# LEDboard.net
KiCad netlist of a schematic drawn in EAGLE
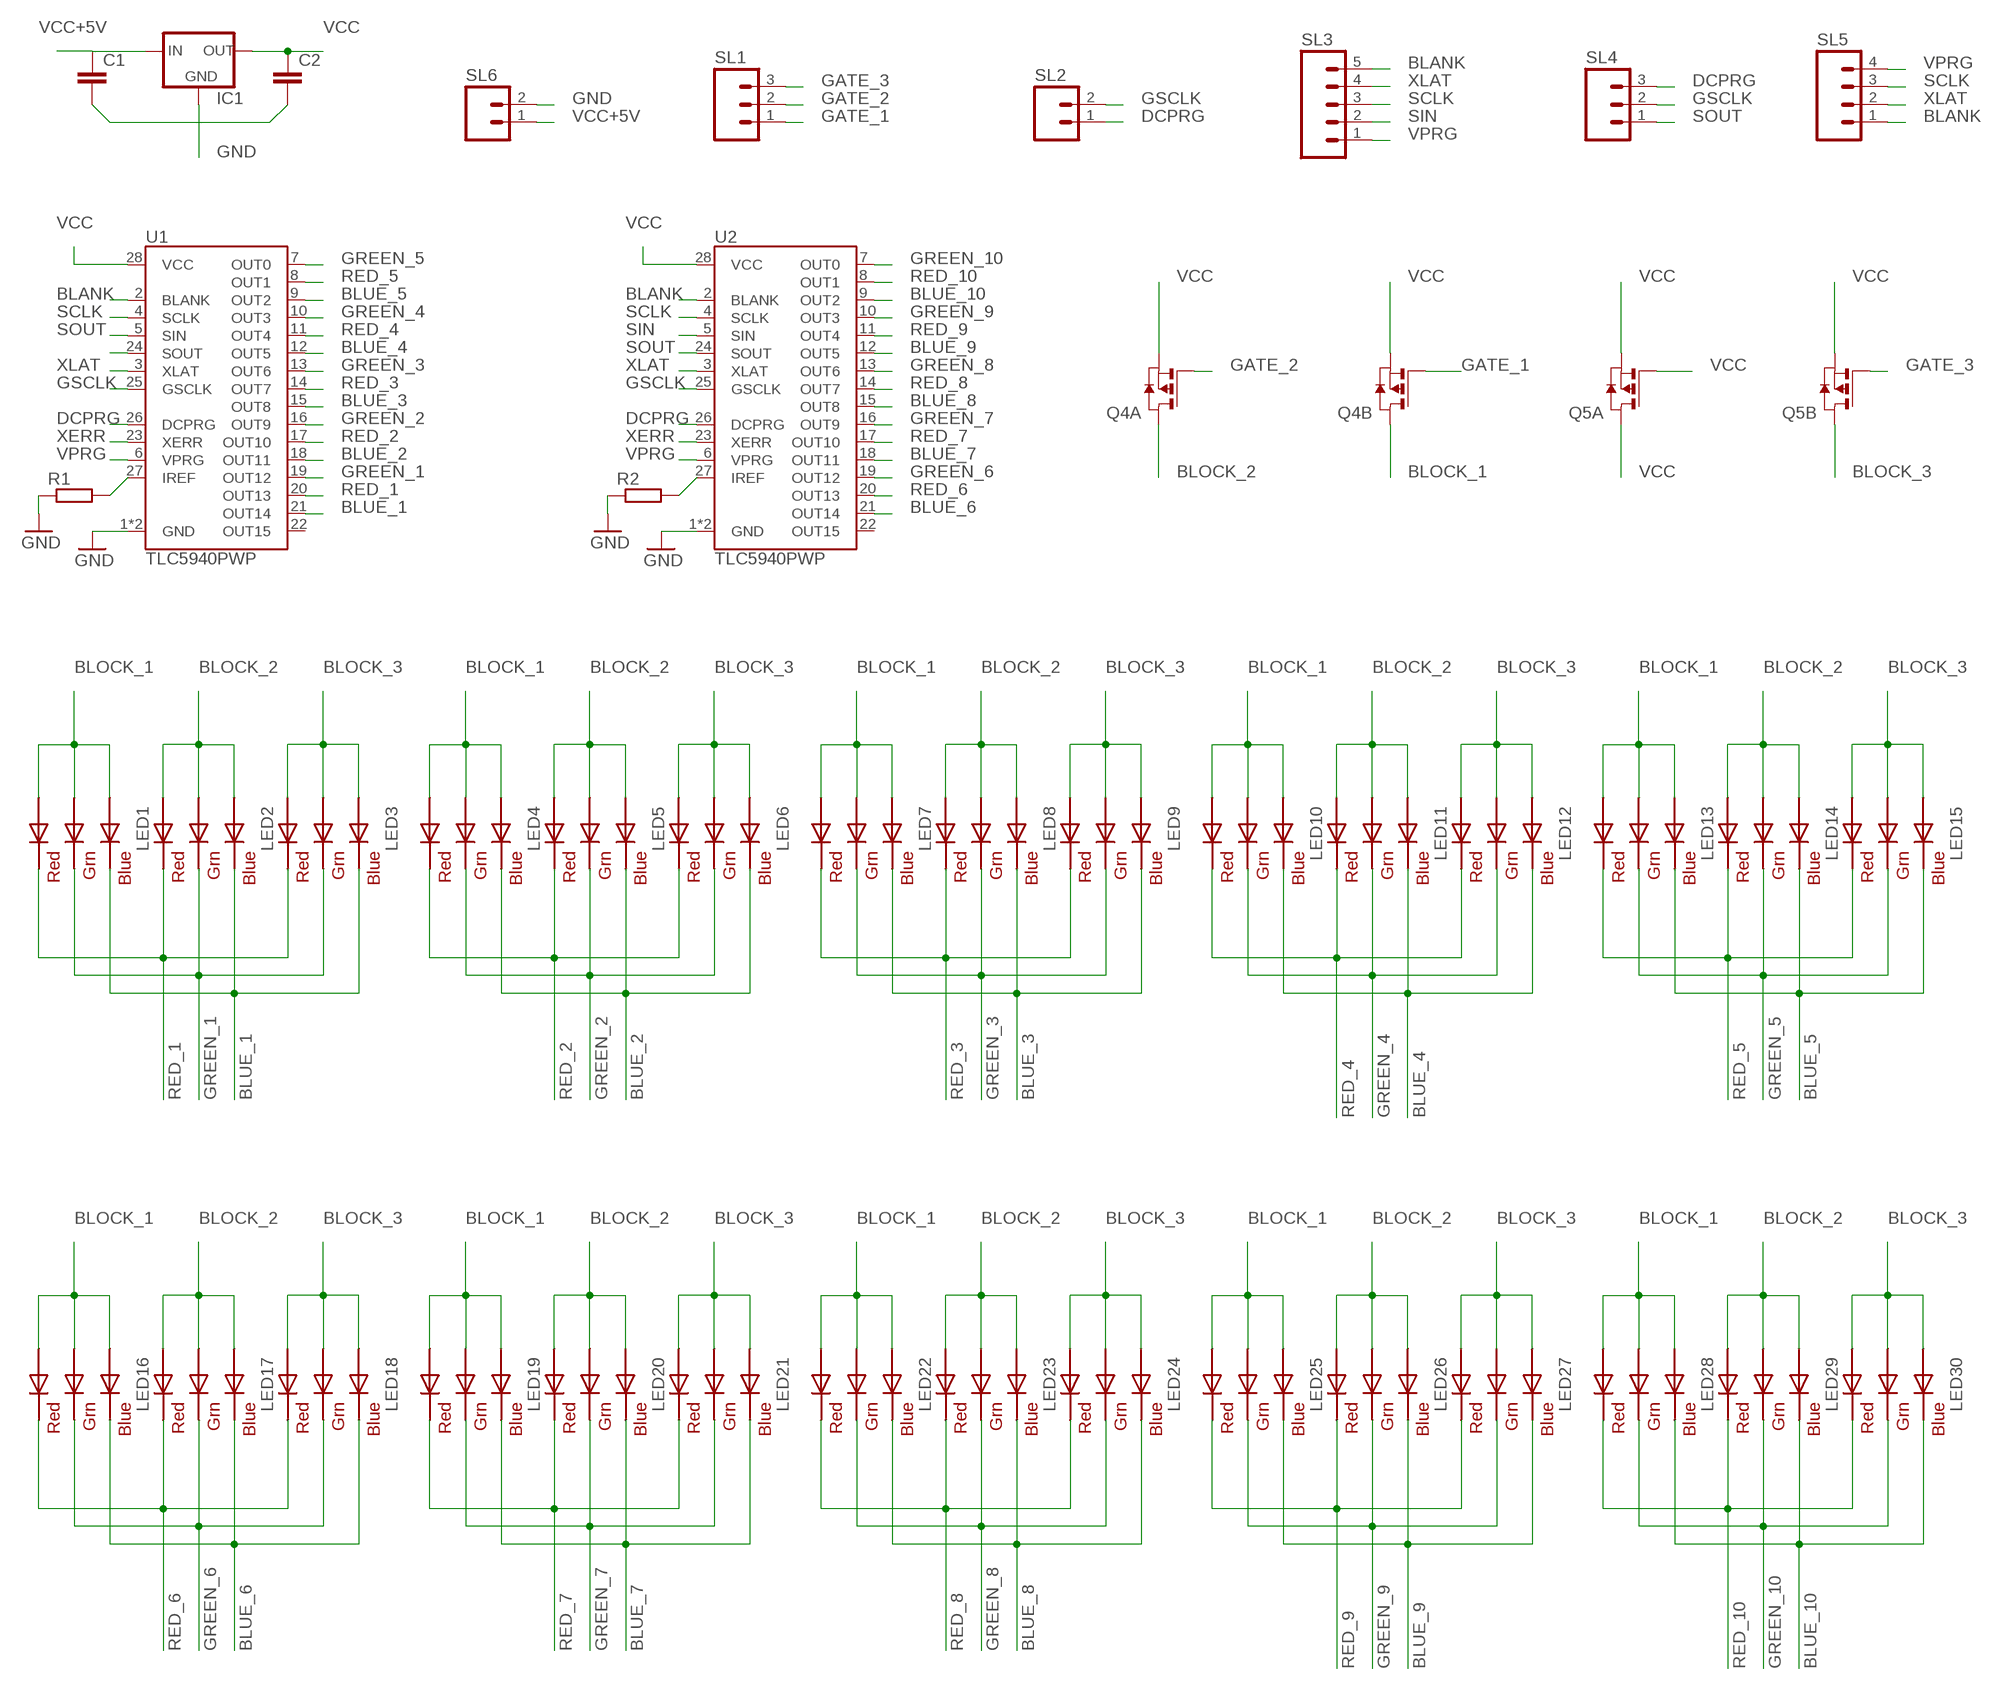
[diagram p0: schematic, sheet 1]

(export (version "E")
  (design (tool "Eeschema 10.0.6"))
  (components
    (comp (ref "C1")
      (value "C-EU050-025X075")
      (footprint "eagle-import:C050-025X075")
      (libsource (lib "eagle-import") (part "C-EU050-025X075"))
    )
    (comp (ref "C2")
      (value "C-EU050-025X075")
      (footprint "eagle-import:C050-025X075")
      (libsource (lib "eagle-import") (part "C-EU050-025X075"))
    )
    (comp (ref "IC1")
      (value "78XXL")
      (footprint "eagle-import:78XXL")
      (libsource (lib "eagle-import") (part "78XXL"))
    )
    (comp (ref "LED1")
      (value "RGBLED5050")
      (footprint "eagle-import:RGBLED5050")
      (libsource (lib "eagle-import") (part "RGBLED5050"))
    )
    (comp (ref "LED2")
      (value "RGBLED5050")
      (footprint "eagle-import:RGBLED5050")
      (libsource (lib "eagle-import") (part "RGBLED5050"))
    )
    (comp (ref "LED3")
      (value "RGBLED5050")
      (footprint "eagle-import:RGBLED5050")
      (libsource (lib "eagle-import") (part "RGBLED5050"))
    )
    (comp (ref "LED4")
      (value "RGBLED5050")
      (footprint "eagle-import:RGBLED5050")
      (libsource (lib "eagle-import") (part "RGBLED5050"))
    )
    (comp (ref "LED5")
      (value "RGBLED5050")
      (footprint "eagle-import:RGBLED5050")
      (libsource (lib "eagle-import") (part "RGBLED5050"))
    )
    (comp (ref "LED6")
      (value "RGBLED5050")
      (footprint "eagle-import:RGBLED5050")
      (libsource (lib "eagle-import") (part "RGBLED5050"))
    )
    (comp (ref "LED7")
      (value "RGBLED5050")
      (footprint "eagle-import:RGBLED5050")
      (libsource (lib "eagle-import") (part "RGBLED5050"))
    )
    (comp (ref "LED8")
      (value "RGBLED5050")
      (footprint "eagle-import:RGBLED5050")
      (libsource (lib "eagle-import") (part "RGBLED5050"))
    )
    (comp (ref "LED9")
      (value "RGBLED5050")
      (footprint "eagle-import:RGBLED5050")
      (libsource (lib "eagle-import") (part "RGBLED5050"))
    )
    (comp (ref "LED10")
      (value "RGBLED5050")
      (footprint "eagle-import:RGBLED5050")
      (libsource (lib "eagle-import") (part "RGBLED5050"))
    )
    (comp (ref "LED11")
      (value "RGBLED5050")
      (footprint "eagle-import:RGBLED5050")
      (libsource (lib "eagle-import") (part "RGBLED5050"))
    )
    (comp (ref "LED12")
      (value "RGBLED5050")
      (footprint "eagle-import:RGBLED5050")
      (libsource (lib "eagle-import") (part "RGBLED5050"))
    )
    (comp (ref "LED13")
      (value "RGBLED5050")
      (footprint "eagle-import:RGBLED5050")
      (libsource (lib "eagle-import") (part "RGBLED5050"))
    )
    (comp (ref "LED14")
      (value "RGBLED5050")
      (footprint "eagle-import:RGBLED5050")
      (libsource (lib "eagle-import") (part "RGBLED5050"))
    )
    (comp (ref "LED15")
      (value "RGBLED5050")
      (footprint "eagle-import:RGBLED5050")
      (libsource (lib "eagle-import") (part "RGBLED5050"))
    )
    (comp (ref "LED16")
      (value "RGBLED5050")
      (footprint "eagle-import:RGBLED5050")
      (libsource (lib "eagle-import") (part "RGBLED5050"))
    )
    (comp (ref "LED17")
      (value "RGBLED5050")
      (footprint "eagle-import:RGBLED5050")
      (libsource (lib "eagle-import") (part "RGBLED5050"))
    )
    (comp (ref "LED18")
      (value "RGBLED5050")
      (footprint "eagle-import:RGBLED5050")
      (libsource (lib "eagle-import") (part "RGBLED5050"))
    )
    (comp (ref "LED19")
      (value "RGBLED5050")
      (footprint "eagle-import:RGBLED5050")
      (libsource (lib "eagle-import") (part "RGBLED5050"))
    )
    (comp (ref "LED20")
      (value "RGBLED5050")
      (footprint "eagle-import:RGBLED5050")
      (libsource (lib "eagle-import") (part "RGBLED5050"))
    )
    (comp (ref "LED21")
      (value "RGBLED5050")
      (footprint "eagle-import:RGBLED5050")
      (libsource (lib "eagle-import") (part "RGBLED5050"))
    )
    (comp (ref "LED22")
      (value "RGBLED5050")
      (footprint "eagle-import:RGBLED5050")
      (libsource (lib "eagle-import") (part "RGBLED5050"))
    )
    (comp (ref "LED23")
      (value "RGBLED5050")
      (footprint "eagle-import:RGBLED5050")
      (libsource (lib "eagle-import") (part "RGBLED5050"))
    )
    (comp (ref "LED24")
      (value "RGBLED5050")
      (footprint "eagle-import:RGBLED5050")
      (libsource (lib "eagle-import") (part "RGBLED5050"))
    )
    (comp (ref "LED25")
      (value "RGBLED5050")
      (footprint "eagle-import:RGBLED5050")
      (libsource (lib "eagle-import") (part "RGBLED5050"))
    )
    (comp (ref "LED26")
      (value "RGBLED5050")
      (footprint "eagle-import:RGBLED5050")
      (libsource (lib "eagle-import") (part "RGBLED5050"))
    )
    (comp (ref "LED27")
      (value "RGBLED5050")
      (footprint "eagle-import:RGBLED5050")
      (libsource (lib "eagle-import") (part "RGBLED5050"))
    )
    (comp (ref "LED28")
      (value "RGBLED5050")
      (footprint "eagle-import:RGBLED5050")
      (libsource (lib "eagle-import") (part "RGBLED5050"))
    )
    (comp (ref "LED29")
      (value "RGBLED5050")
      (footprint "eagle-import:RGBLED5050")
      (libsource (lib "eagle-import") (part "RGBLED5050"))
    )
    (comp (ref "LED30")
      (value "RGBLED5050")
      (footprint "eagle-import:RGBLED5050")
      (libsource (lib "eagle-import") (part "RGBLED5050"))
    )
    (comp (ref "Q4")
      (value "PN_MOSFET-SO8")
      (footprint "eagle-import:SO8")
      (libsource (lib "eagle-import") (part "PN_MOSFET-SO8"))
    )
    (comp (ref "Q5")
      (value "PN_MOSFET-SO8")
      (footprint "eagle-import:SO8")
      (libsource (lib "eagle-import") (part "PN_MOSFET-SO8"))
    )
    (comp (ref "R1")
      (value "R-EU_M1406")
      (footprint "eagle-import:M1406")
      (libsource (lib "eagle-import") (part "R-EU_M1406"))
    )
    (comp (ref "R2")
      (value "R-EU_M1406")
      (footprint "eagle-import:M1406")
      (libsource (lib "eagle-import") (part "R-EU_M1406"))
    )
    (comp (ref "SL1")
      (value "M03")
      (footprint "eagle-import:03P")
      (libsource (lib "eagle-import") (part "M03"))
    )
    (comp (ref "SL2")
      (value "M02")
      (footprint "eagle-import:02P")
      (libsource (lib "eagle-import") (part "M02"))
    )
    (comp (ref "SL3")
      (value "M05")
      (footprint "eagle-import:05P")
      (libsource (lib "eagle-import") (part "M05"))
    )
    (comp (ref "SL4")
      (value "M03")
      (footprint "eagle-import:03P")
      (libsource (lib "eagle-import") (part "M03"))
    )
    (comp (ref "SL5")
      (value "M04")
      (footprint "eagle-import:04P")
      (libsource (lib "eagle-import") (part "M04"))
    )
    (comp (ref "SL6")
      (value "M02")
      (footprint "eagle-import:02P")
      (libsource (lib "eagle-import") (part "M02"))
    )
    (comp (ref "U1")
      (value "TLC5940PWP")
      (footprint "eagle-import:TSSOP28-GROUNDPAD")
      (libsource (lib "eagle-import") (part "TLC5940PWP"))
    )
    (comp (ref "U2")
      (value "TLC5940PWP")
      (footprint "eagle-import:TSSOP28-GROUNDPAD")
      (libsource (lib "eagle-import") (part "TLC5940PWP"))
    )
  )
  (nets
    (net (code "1") (name "/BLANK") (class "Default")
      (node (ref "SL3") (pin "5") (pinfunction "5_5") (pintype "passive"))
      (node (ref "SL5") (pin "1") (pinfunction "1_1") (pintype "passive"))
      (node (ref "U1") (pin "2") (pinfunction "BLANK_2") (pintype "bidirectional"))
      (node (ref "U2") (pin "2") (pinfunction "BLANK_2") (pintype "bidirectional"))
    )
    (net (code "2") (name "/BLOCK_1") (class "Default")
      (node (ref "LED1") (pin "1") (pinfunction "GREEN_A_1") (pintype "bidirectional"))
      (node (ref "LED1") (pin "2") (pinfunction "RED_A_2") (pintype "bidirectional"))
      (node (ref "LED1") (pin "3") (pinfunction "BLUE_A_3") (pintype "bidirectional"))
      (node (ref "LED10") (pin "1") (pinfunction "GREEN_A_1") (pintype "bidirectional"))
      (node (ref "LED10") (pin "2") (pinfunction "RED_A_2") (pintype "bidirectional"))
      (node (ref "LED10") (pin "3") (pinfunction "BLUE_A_3") (pintype "bidirectional"))
      (node (ref "LED13") (pin "1") (pinfunction "GREEN_A_1") (pintype "bidirectional"))
      (node (ref "LED13") (pin "2") (pinfunction "RED_A_2") (pintype "bidirectional"))
      (node (ref "LED13") (pin "3") (pinfunction "BLUE_A_3") (pintype "bidirectional"))
      (node (ref "LED16") (pin "1") (pinfunction "GREEN_A_1") (pintype "bidirectional"))
      (node (ref "LED16") (pin "2") (pinfunction "RED_A_2") (pintype "bidirectional"))
      (node (ref "LED16") (pin "3") (pinfunction "BLUE_A_3") (pintype "bidirectional"))
      (node (ref "LED19") (pin "1") (pinfunction "GREEN_A_1") (pintype "bidirectional"))
      (node (ref "LED19") (pin "2") (pinfunction "RED_A_2") (pintype "bidirectional"))
      (node (ref "LED19") (pin "3") (pinfunction "BLUE_A_3") (pintype "bidirectional"))
      (node (ref "LED22") (pin "1") (pinfunction "GREEN_A_1") (pintype "bidirectional"))
      (node (ref "LED22") (pin "2") (pinfunction "RED_A_2") (pintype "bidirectional"))
      (node (ref "LED22") (pin "3") (pinfunction "BLUE_A_3") (pintype "bidirectional"))
      (node (ref "LED25") (pin "1") (pinfunction "GREEN_A_1") (pintype "bidirectional"))
      (node (ref "LED25") (pin "2") (pinfunction "RED_A_2") (pintype "bidirectional"))
      (node (ref "LED25") (pin "3") (pinfunction "BLUE_A_3") (pintype "bidirectional"))
      (node (ref "LED28") (pin "1") (pinfunction "GREEN_A_1") (pintype "bidirectional"))
      (node (ref "LED28") (pin "2") (pinfunction "RED_A_2") (pintype "bidirectional"))
      (node (ref "LED28") (pin "3") (pinfunction "BLUE_A_3") (pintype "bidirectional"))
      (node (ref "LED4") (pin "1") (pinfunction "GREEN_A_1") (pintype "bidirectional"))
      (node (ref "LED4") (pin "2") (pinfunction "RED_A_2") (pintype "bidirectional"))
      (node (ref "LED4") (pin "3") (pinfunction "BLUE_A_3") (pintype "bidirectional"))
      (node (ref "LED7") (pin "1") (pinfunction "GREEN_A_1") (pintype "bidirectional"))
      (node (ref "LED7") (pin "2") (pinfunction "RED_A_2") (pintype "bidirectional"))
      (node (ref "LED7") (pin "3") (pinfunction "BLUE_A_3") (pintype "bidirectional"))
      (node (ref "Q4") (pin "5") (pinfunction "D_5") (pintype "passive"))
      (node (ref "Q4") (pin "6") (pinfunction "D_6") (pintype "passive"))
    )
    (net (code "3") (name "/BLOCK_2") (class "Default")
      (node (ref "LED11") (pin "1") (pinfunction "GREEN_A_1") (pintype "bidirectional"))
      (node (ref "LED11") (pin "2") (pinfunction "RED_A_2") (pintype "bidirectional"))
      (node (ref "LED11") (pin "3") (pinfunction "BLUE_A_3") (pintype "bidirectional"))
      (node (ref "LED14") (pin "1") (pinfunction "GREEN_A_1") (pintype "bidirectional"))
      (node (ref "LED14") (pin "2") (pinfunction "RED_A_2") (pintype "bidirectional"))
      (node (ref "LED14") (pin "3") (pinfunction "BLUE_A_3") (pintype "bidirectional"))
      (node (ref "LED17") (pin "1") (pinfunction "GREEN_A_1") (pintype "bidirectional"))
      (node (ref "LED17") (pin "2") (pinfunction "RED_A_2") (pintype "bidirectional"))
      (node (ref "LED17") (pin "3") (pinfunction "BLUE_A_3") (pintype "bidirectional"))
      (node (ref "LED2") (pin "1") (pinfunction "GREEN_A_1") (pintype "bidirectional"))
      (node (ref "LED2") (pin "2") (pinfunction "RED_A_2") (pintype "bidirectional"))
      (node (ref "LED2") (pin "3") (pinfunction "BLUE_A_3") (pintype "bidirectional"))
      (node (ref "LED20") (pin "1") (pinfunction "GREEN_A_1") (pintype "bidirectional"))
      (node (ref "LED20") (pin "2") (pinfunction "RED_A_2") (pintype "bidirectional"))
      (node (ref "LED20") (pin "3") (pinfunction "BLUE_A_3") (pintype "bidirectional"))
      (node (ref "LED23") (pin "1") (pinfunction "GREEN_A_1") (pintype "bidirectional"))
      (node (ref "LED23") (pin "2") (pinfunction "RED_A_2") (pintype "bidirectional"))
      (node (ref "LED23") (pin "3") (pinfunction "BLUE_A_3") (pintype "bidirectional"))
      (node (ref "LED26") (pin "1") (pinfunction "GREEN_A_1") (pintype "bidirectional"))
      (node (ref "LED26") (pin "2") (pinfunction "RED_A_2") (pintype "bidirectional"))
      (node (ref "LED26") (pin "3") (pinfunction "BLUE_A_3") (pintype "bidirectional"))
      (node (ref "LED29") (pin "1") (pinfunction "GREEN_A_1") (pintype "bidirectional"))
      (node (ref "LED29") (pin "2") (pinfunction "RED_A_2") (pintype "bidirectional"))
      (node (ref "LED29") (pin "3") (pinfunction "BLUE_A_3") (pintype "bidirectional"))
      (node (ref "LED5") (pin "1") (pinfunction "GREEN_A_1") (pintype "bidirectional"))
      (node (ref "LED5") (pin "2") (pinfunction "RED_A_2") (pintype "bidirectional"))
      (node (ref "LED5") (pin "3") (pinfunction "BLUE_A_3") (pintype "bidirectional"))
      (node (ref "LED8") (pin "1") (pinfunction "GREEN_A_1") (pintype "bidirectional"))
      (node (ref "LED8") (pin "2") (pinfunction "RED_A_2") (pintype "bidirectional"))
      (node (ref "LED8") (pin "3") (pinfunction "BLUE_A_3") (pintype "bidirectional"))
      (node (ref "Q4") (pin "7") (pinfunction "D_7") (pintype "passive"))
      (node (ref "Q4") (pin "8") (pinfunction "D_8") (pintype "passive"))
    )
    (net (code "4") (name "/BLOCK_3") (class "Default")
      (node (ref "LED12") (pin "1") (pinfunction "GREEN_A_1") (pintype "bidirectional"))
      (node (ref "LED12") (pin "2") (pinfunction "RED_A_2") (pintype "bidirectional"))
      (node (ref "LED12") (pin "3") (pinfunction "BLUE_A_3") (pintype "bidirectional"))
      (node (ref "LED15") (pin "1") (pinfunction "GREEN_A_1") (pintype "bidirectional"))
      (node (ref "LED15") (pin "2") (pinfunction "RED_A_2") (pintype "bidirectional"))
      (node (ref "LED15") (pin "3") (pinfunction "BLUE_A_3") (pintype "bidirectional"))
      (node (ref "LED18") (pin "1") (pinfunction "GREEN_A_1") (pintype "bidirectional"))
      (node (ref "LED18") (pin "2") (pinfunction "RED_A_2") (pintype "bidirectional"))
      (node (ref "LED18") (pin "3") (pinfunction "BLUE_A_3") (pintype "bidirectional"))
      (node (ref "LED21") (pin "1") (pinfunction "GREEN_A_1") (pintype "bidirectional"))
      (node (ref "LED21") (pin "2") (pinfunction "RED_A_2") (pintype "bidirectional"))
      (node (ref "LED21") (pin "3") (pinfunction "BLUE_A_3") (pintype "bidirectional"))
      (node (ref "LED24") (pin "1") (pinfunction "GREEN_A_1") (pintype "bidirectional"))
      (node (ref "LED24") (pin "2") (pinfunction "RED_A_2") (pintype "bidirectional"))
      (node (ref "LED24") (pin "3") (pinfunction "BLUE_A_3") (pintype "bidirectional"))
      (node (ref "LED27") (pin "1") (pinfunction "GREEN_A_1") (pintype "bidirectional"))
      (node (ref "LED27") (pin "2") (pinfunction "RED_A_2") (pintype "bidirectional"))
      (node (ref "LED27") (pin "3") (pinfunction "BLUE_A_3") (pintype "bidirectional"))
      (node (ref "LED3") (pin "1") (pinfunction "GREEN_A_1") (pintype "bidirectional"))
      (node (ref "LED3") (pin "2") (pinfunction "RED_A_2") (pintype "bidirectional"))
      (node (ref "LED3") (pin "3") (pinfunction "BLUE_A_3") (pintype "bidirectional"))
      (node (ref "LED30") (pin "1") (pinfunction "GREEN_A_1") (pintype "bidirectional"))
      (node (ref "LED30") (pin "2") (pinfunction "RED_A_2") (pintype "bidirectional"))
      (node (ref "LED30") (pin "3") (pinfunction "BLUE_A_3") (pintype "bidirectional"))
      (node (ref "LED6") (pin "1") (pinfunction "GREEN_A_1") (pintype "bidirectional"))
      (node (ref "LED6") (pin "2") (pinfunction "RED_A_2") (pintype "bidirectional"))
      (node (ref "LED6") (pin "3") (pinfunction "BLUE_A_3") (pintype "bidirectional"))
      (node (ref "LED9") (pin "1") (pinfunction "GREEN_A_1") (pintype "bidirectional"))
      (node (ref "LED9") (pin "2") (pinfunction "RED_A_2") (pintype "bidirectional"))
      (node (ref "LED9") (pin "3") (pinfunction "BLUE_A_3") (pintype "bidirectional"))
      (node (ref "Q5") (pin "5") (pinfunction "D_5") (pintype "passive"))
      (node (ref "Q5") (pin "6") (pinfunction "D_6") (pintype "passive"))
    )
    (net (code "5") (name "/BLUE_1") (class "Default")
      (node (ref "LED1") (pin "4") (pinfunction "BLUE_C_4") (pintype "bidirectional"))
      (node (ref "LED2") (pin "4") (pinfunction "BLUE_C_4") (pintype "bidirectional"))
      (node (ref "LED3") (pin "4") (pinfunction "BLUE_C_4") (pintype "bidirectional"))
      (node (ref "U1") (pin "21") (pinfunction "OUT14_21") (pintype "bidirectional"))
    )
    (net (code "6") (name "/BLUE_2") (class "Default")
      (node (ref "LED4") (pin "4") (pinfunction "BLUE_C_4") (pintype "bidirectional"))
      (node (ref "LED5") (pin "4") (pinfunction "BLUE_C_4") (pintype "bidirectional"))
      (node (ref "LED6") (pin "4") (pinfunction "BLUE_C_4") (pintype "bidirectional"))
      (node (ref "U1") (pin "18") (pinfunction "OUT11_18") (pintype "bidirectional"))
    )
    (net (code "7") (name "/BLUE_3") (class "Default")
      (node (ref "LED7") (pin "4") (pinfunction "BLUE_C_4") (pintype "bidirectional"))
      (node (ref "LED8") (pin "4") (pinfunction "BLUE_C_4") (pintype "bidirectional"))
      (node (ref "LED9") (pin "4") (pinfunction "BLUE_C_4") (pintype "bidirectional"))
      (node (ref "U1") (pin "15") (pinfunction "OUT8_15") (pintype "bidirectional"))
    )
    (net (code "8") (name "/BLUE_4") (class "Default")
      (node (ref "LED10") (pin "4") (pinfunction "BLUE_C_4") (pintype "bidirectional"))
      (node (ref "LED11") (pin "4") (pinfunction "BLUE_C_4") (pintype "bidirectional"))
      (node (ref "LED12") (pin "4") (pinfunction "BLUE_C_4") (pintype "bidirectional"))
      (node (ref "U1") (pin "12") (pinfunction "OUT5_12") (pintype "bidirectional"))
    )
    (net (code "9") (name "/BLUE_5") (class "Default")
      (node (ref "LED13") (pin "4") (pinfunction "BLUE_C_4") (pintype "bidirectional"))
      (node (ref "LED14") (pin "4") (pinfunction "BLUE_C_4") (pintype "bidirectional"))
      (node (ref "LED15") (pin "4") (pinfunction "BLUE_C_4") (pintype "bidirectional"))
      (node (ref "U1") (pin "9") (pinfunction "OUT2_9") (pintype "bidirectional"))
    )
    (net (code "10") (name "/BLUE_6") (class "Default")
      (node (ref "LED16") (pin "4") (pinfunction "BLUE_C_4") (pintype "bidirectional"))
      (node (ref "LED17") (pin "4") (pinfunction "BLUE_C_4") (pintype "bidirectional"))
      (node (ref "LED18") (pin "4") (pinfunction "BLUE_C_4") (pintype "bidirectional"))
      (node (ref "U2") (pin "21") (pinfunction "OUT14_21") (pintype "bidirectional"))
    )
    (net (code "11") (name "/BLUE_7") (class "Default")
      (node (ref "LED19") (pin "4") (pinfunction "BLUE_C_4") (pintype "bidirectional"))
      (node (ref "LED20") (pin "4") (pinfunction "BLUE_C_4") (pintype "bidirectional"))
      (node (ref "LED21") (pin "4") (pinfunction "BLUE_C_4") (pintype "bidirectional"))
      (node (ref "U2") (pin "18") (pinfunction "OUT11_18") (pintype "bidirectional"))
    )
    (net (code "12") (name "/BLUE_8") (class "Default")
      (node (ref "LED22") (pin "4") (pinfunction "BLUE_C_4") (pintype "bidirectional"))
      (node (ref "LED23") (pin "4") (pinfunction "BLUE_C_4") (pintype "bidirectional"))
      (node (ref "LED24") (pin "4") (pinfunction "BLUE_C_4") (pintype "bidirectional"))
      (node (ref "U2") (pin "15") (pinfunction "OUT8_15") (pintype "bidirectional"))
    )
    (net (code "13") (name "/BLUE_9") (class "Default")
      (node (ref "LED25") (pin "4") (pinfunction "BLUE_C_4") (pintype "bidirectional"))
      (node (ref "LED26") (pin "4") (pinfunction "BLUE_C_4") (pintype "bidirectional"))
      (node (ref "LED27") (pin "4") (pinfunction "BLUE_C_4") (pintype "bidirectional"))
      (node (ref "U2") (pin "12") (pinfunction "OUT5_12") (pintype "bidirectional"))
    )
    (net (code "14") (name "/BLUE_10") (class "Default")
      (node (ref "LED28") (pin "4") (pinfunction "BLUE_C_4") (pintype "bidirectional"))
      (node (ref "LED29") (pin "4") (pinfunction "BLUE_C_4") (pintype "bidirectional"))
      (node (ref "LED30") (pin "4") (pinfunction "BLUE_C_4") (pintype "bidirectional"))
      (node (ref "U2") (pin "9") (pinfunction "OUT2_9") (pintype "bidirectional"))
    )
    (net (code "15") (name "/DCPRG") (class "Default")
      (node (ref "SL2") (pin "1") (pinfunction "1_1") (pintype "passive"))
      (node (ref "SL4") (pin "3") (pinfunction "3_3") (pintype "passive"))
      (node (ref "U1") (pin "26") (pinfunction "DCPRG_26") (pintype "bidirectional"))
      (node (ref "U2") (pin "26") (pinfunction "DCPRG_26") (pintype "bidirectional"))
    )
    (net (code "16") (name "/GATE_1") (class "Default")
      (node (ref "Q4") (pin "4") (pinfunction "G_4") (pintype "passive"))
      (node (ref "SL1") (pin "1") (pinfunction "1_1") (pintype "passive"))
    )
    (net (code "17") (name "/GATE_2") (class "Default")
      (node (ref "Q4") (pin "2") (pinfunction "G_2") (pintype "passive"))
      (node (ref "SL1") (pin "2") (pinfunction "2_2") (pintype "passive"))
    )
    (net (code "18") (name "/GATE_3") (class "Default")
      (node (ref "Q5") (pin "4") (pinfunction "G_4") (pintype "passive"))
      (node (ref "SL1") (pin "3") (pinfunction "3_3") (pintype "passive"))
    )
    (net (code "19") (name "/GREEN_1") (class "Default")
      (node (ref "LED1") (pin "6") (pinfunction "GREEN_C_6") (pintype "bidirectional"))
      (node (ref "LED2") (pin "6") (pinfunction "GREEN_C_6") (pintype "bidirectional"))
      (node (ref "LED3") (pin "6") (pinfunction "GREEN_C_6") (pintype "bidirectional"))
      (node (ref "U1") (pin "19") (pinfunction "OUT12_19") (pintype "bidirectional"))
    )
    (net (code "20") (name "/GREEN_2") (class "Default")
      (node (ref "LED4") (pin "6") (pinfunction "GREEN_C_6") (pintype "bidirectional"))
      (node (ref "LED5") (pin "6") (pinfunction "GREEN_C_6") (pintype "bidirectional"))
      (node (ref "LED6") (pin "6") (pinfunction "GREEN_C_6") (pintype "bidirectional"))
      (node (ref "U1") (pin "16") (pinfunction "OUT9_16") (pintype "bidirectional"))
    )
    (net (code "21") (name "/GREEN_3") (class "Default")
      (node (ref "LED7") (pin "6") (pinfunction "GREEN_C_6") (pintype "bidirectional"))
      (node (ref "LED8") (pin "6") (pinfunction "GREEN_C_6") (pintype "bidirectional"))
      (node (ref "LED9") (pin "6") (pinfunction "GREEN_C_6") (pintype "bidirectional"))
      (node (ref "U1") (pin "13") (pinfunction "OUT6_13") (pintype "bidirectional"))
    )
    (net (code "22") (name "/GREEN_4") (class "Default")
      (node (ref "LED10") (pin "6") (pinfunction "GREEN_C_6") (pintype "bidirectional"))
      (node (ref "LED11") (pin "6") (pinfunction "GREEN_C_6") (pintype "bidirectional"))
      (node (ref "LED12") (pin "6") (pinfunction "GREEN_C_6") (pintype "bidirectional"))
      (node (ref "U1") (pin "10") (pinfunction "OUT3_10") (pintype "bidirectional"))
    )
    (net (code "23") (name "/GREEN_5") (class "Default")
      (node (ref "LED13") (pin "6") (pinfunction "GREEN_C_6") (pintype "bidirectional"))
      (node (ref "LED14") (pin "6") (pinfunction "GREEN_C_6") (pintype "bidirectional"))
      (node (ref "LED15") (pin "6") (pinfunction "GREEN_C_6") (pintype "bidirectional"))
      (node (ref "U1") (pin "7") (pinfunction "OUT0_7") (pintype "bidirectional"))
    )
    (net (code "24") (name "/GREEN_6") (class "Default")
      (node (ref "LED16") (pin "6") (pinfunction "GREEN_C_6") (pintype "bidirectional"))
      (node (ref "LED17") (pin "6") (pinfunction "GREEN_C_6") (pintype "bidirectional"))
      (node (ref "LED18") (pin "6") (pinfunction "GREEN_C_6") (pintype "bidirectional"))
      (node (ref "U2") (pin "19") (pinfunction "OUT12_19") (pintype "bidirectional"))
    )
    (net (code "25") (name "/GREEN_7") (class "Default")
      (node (ref "LED19") (pin "6") (pinfunction "GREEN_C_6") (pintype "bidirectional"))
      (node (ref "LED20") (pin "6") (pinfunction "GREEN_C_6") (pintype "bidirectional"))
      (node (ref "LED21") (pin "6") (pinfunction "GREEN_C_6") (pintype "bidirectional"))
      (node (ref "U2") (pin "16") (pinfunction "OUT9_16") (pintype "bidirectional"))
    )
    (net (code "26") (name "/GREEN_8") (class "Default")
      (node (ref "LED22") (pin "6") (pinfunction "GREEN_C_6") (pintype "bidirectional"))
      (node (ref "LED23") (pin "6") (pinfunction "GREEN_C_6") (pintype "bidirectional"))
      (node (ref "LED24") (pin "6") (pinfunction "GREEN_C_6") (pintype "bidirectional"))
      (node (ref "U2") (pin "13") (pinfunction "OUT6_13") (pintype "bidirectional"))
    )
    (net (code "27") (name "/GREEN_9") (class "Default")
      (node (ref "LED25") (pin "6") (pinfunction "GREEN_C_6") (pintype "bidirectional"))
      (node (ref "LED26") (pin "6") (pinfunction "GREEN_C_6") (pintype "bidirectional"))
      (node (ref "LED27") (pin "6") (pinfunction "GREEN_C_6") (pintype "bidirectional"))
      (node (ref "U2") (pin "10") (pinfunction "OUT3_10") (pintype "bidirectional"))
    )
    (net (code "28") (name "/GREEN_10") (class "Default")
      (node (ref "LED28") (pin "6") (pinfunction "GREEN_C_6") (pintype "bidirectional"))
      (node (ref "LED29") (pin "6") (pinfunction "GREEN_C_6") (pintype "bidirectional"))
      (node (ref "LED30") (pin "6") (pinfunction "GREEN_C_6") (pintype "bidirectional"))
      (node (ref "U2") (pin "7") (pinfunction "OUT0_7") (pintype "bidirectional"))
    )
    (net (code "29") (name "/GSCLK") (class "Default")
      (node (ref "SL2") (pin "2") (pinfunction "2_2") (pintype "passive"))
      (node (ref "SL4") (pin "2") (pinfunction "2_2") (pintype "passive"))
      (node (ref "U1") (pin "25") (pinfunction "GSCLK_25") (pintype "bidirectional"))
      (node (ref "U2") (pin "25") (pinfunction "GSCLK_25") (pintype "bidirectional"))
    )
    (net (code "30") (name "/RED_1") (class "Default")
      (node (ref "LED1") (pin "5") (pinfunction "RED_C_5") (pintype "bidirectional"))
      (node (ref "LED2") (pin "5") (pinfunction "RED_C_5") (pintype "bidirectional"))
      (node (ref "LED3") (pin "5") (pinfunction "RED_C_5") (pintype "bidirectional"))
      (node (ref "U1") (pin "20") (pinfunction "OUT13_20") (pintype "bidirectional"))
    )
    (net (code "31") (name "/RED_2") (class "Default")
      (node (ref "LED4") (pin "5") (pinfunction "RED_C_5") (pintype "bidirectional"))
      (node (ref "LED5") (pin "5") (pinfunction "RED_C_5") (pintype "bidirectional"))
      (node (ref "LED6") (pin "5") (pinfunction "RED_C_5") (pintype "bidirectional"))
      (node (ref "U1") (pin "17") (pinfunction "OUT10_17") (pintype "bidirectional"))
    )
    (net (code "32") (name "/RED_3") (class "Default")
      (node (ref "LED7") (pin "5") (pinfunction "RED_C_5") (pintype "bidirectional"))
      (node (ref "LED8") (pin "5") (pinfunction "RED_C_5") (pintype "bidirectional"))
      (node (ref "LED9") (pin "5") (pinfunction "RED_C_5") (pintype "bidirectional"))
      (node (ref "U1") (pin "14") (pinfunction "OUT7_14") (pintype "bidirectional"))
    )
    (net (code "33") (name "/RED_4") (class "Default")
      (node (ref "LED10") (pin "5") (pinfunction "RED_C_5") (pintype "bidirectional"))
      (node (ref "LED11") (pin "5") (pinfunction "RED_C_5") (pintype "bidirectional"))
      (node (ref "LED12") (pin "5") (pinfunction "RED_C_5") (pintype "bidirectional"))
      (node (ref "U1") (pin "11") (pinfunction "OUT4_11") (pintype "bidirectional"))
    )
    (net (code "34") (name "/RED_5") (class "Default")
      (node (ref "LED13") (pin "5") (pinfunction "RED_C_5") (pintype "bidirectional"))
      (node (ref "LED14") (pin "5") (pinfunction "RED_C_5") (pintype "bidirectional"))
      (node (ref "LED15") (pin "5") (pinfunction "RED_C_5") (pintype "bidirectional"))
      (node (ref "U1") (pin "8") (pinfunction "OUT1_8") (pintype "bidirectional"))
    )
    (net (code "35") (name "/RED_6") (class "Default")
      (node (ref "LED16") (pin "5") (pinfunction "RED_C_5") (pintype "bidirectional"))
      (node (ref "LED17") (pin "5") (pinfunction "RED_C_5") (pintype "bidirectional"))
      (node (ref "LED18") (pin "5") (pinfunction "RED_C_5") (pintype "bidirectional"))
      (node (ref "U2") (pin "20") (pinfunction "OUT13_20") (pintype "bidirectional"))
    )
    (net (code "36") (name "/RED_7") (class "Default")
      (node (ref "LED19") (pin "5") (pinfunction "RED_C_5") (pintype "bidirectional"))
      (node (ref "LED20") (pin "5") (pinfunction "RED_C_5") (pintype "bidirectional"))
      (node (ref "LED21") (pin "5") (pinfunction "RED_C_5") (pintype "bidirectional"))
      (node (ref "U2") (pin "17") (pinfunction "OUT10_17") (pintype "bidirectional"))
    )
    (net (code "37") (name "/RED_8") (class "Default")
      (node (ref "LED22") (pin "5") (pinfunction "RED_C_5") (pintype "bidirectional"))
      (node (ref "LED23") (pin "5") (pinfunction "RED_C_5") (pintype "bidirectional"))
      (node (ref "LED24") (pin "5") (pinfunction "RED_C_5") (pintype "bidirectional"))
      (node (ref "U2") (pin "14") (pinfunction "OUT7_14") (pintype "bidirectional"))
    )
    (net (code "38") (name "/RED_9") (class "Default")
      (node (ref "LED25") (pin "5") (pinfunction "RED_C_5") (pintype "bidirectional"))
      (node (ref "LED26") (pin "5") (pinfunction "RED_C_5") (pintype "bidirectional"))
      (node (ref "LED27") (pin "5") (pinfunction "RED_C_5") (pintype "bidirectional"))
      (node (ref "U2") (pin "11") (pinfunction "OUT4_11") (pintype "bidirectional"))
    )
    (net (code "39") (name "/RED_10") (class "Default")
      (node (ref "LED28") (pin "5") (pinfunction "RED_C_5") (pintype "bidirectional"))
      (node (ref "LED29") (pin "5") (pinfunction "RED_C_5") (pintype "bidirectional"))
      (node (ref "LED30") (pin "5") (pinfunction "RED_C_5") (pintype "bidirectional"))
      (node (ref "U2") (pin "8") (pinfunction "OUT1_8") (pintype "bidirectional"))
    )
    (net (code "40") (name "/SCLK") (class "Default")
      (node (ref "SL3") (pin "3") (pinfunction "3_3") (pintype "passive"))
      (node (ref "SL5") (pin "3") (pinfunction "3_3") (pintype "passive"))
      (node (ref "U1") (pin "4") (pinfunction "SCLK_4") (pintype "bidirectional"))
      (node (ref "U2") (pin "4") (pinfunction "SCLK_4") (pintype "bidirectional"))
    )
    (net (code "41") (name "/SIN") (class "Default")
      (node (ref "SL3") (pin "2") (pinfunction "2_2") (pintype "passive"))
      (node (ref "U2") (pin "5") (pinfunction "SIN_5") (pintype "bidirectional"))
    )
    (net (code "42") (name "/SOUT") (class "Default")
      (node (ref "SL4") (pin "1") (pinfunction "1_1") (pintype "passive"))
      (node (ref "U1") (pin "24") (pinfunction "SOUT_24") (pintype "bidirectional"))
      (node (ref "U1") (pin "5") (pinfunction "SIN_5") (pintype "bidirectional"))
      (node (ref "U2") (pin "24") (pinfunction "SOUT_24") (pintype "bidirectional"))
    )
    (net (code "43") (name "/VCC") (class "Default")
      (node (ref "C2") (pin "1") (pinfunction "1_1") (pintype "passive"))
      (node (ref "IC1") (pin "OUT") (pinfunction "OUT_OUT") (pintype "passive"))
      (node (ref "Q4") (pin "1") (pinfunction "S_1") (pintype "passive"))
      (node (ref "Q4") (pin "3") (pinfunction "S_3") (pintype "passive"))
      (node (ref "Q5") (pin "1") (pinfunction "S_1") (pintype "passive"))
      (node (ref "Q5") (pin "2") (pinfunction "G_2") (pintype "passive"))
      (node (ref "Q5") (pin "3") (pinfunction "S_3") (pintype "passive"))
      (node (ref "Q5") (pin "7") (pinfunction "D_7") (pintype "passive"))
      (node (ref "Q5") (pin "8") (pinfunction "D_8") (pintype "passive"))
      (node (ref "U1") (pin "28") (pinfunction "VCC_28") (pintype "bidirectional"))
      (node (ref "U2") (pin "28") (pinfunction "VCC_28") (pintype "bidirectional"))
    )
    (net (code "44") (name "/VCC+5V") (class "Default")
      (node (ref "C1") (pin "1") (pinfunction "1_1") (pintype "passive"))
      (node (ref "IC1") (pin "IN") (pinfunction "IN_IN") (pintype "input"))
      (node (ref "SL6") (pin "1") (pinfunction "1_1") (pintype "passive"))
    )
    (net (code "45") (name "/VPRG") (class "Default")
      (node (ref "SL3") (pin "1") (pinfunction "1_1") (pintype "passive"))
      (node (ref "SL5") (pin "4") (pinfunction "4_4") (pintype "passive"))
      (node (ref "U1") (pin "6") (pinfunction "VPRG_6") (pintype "bidirectional"))
      (node (ref "U2") (pin "6") (pinfunction "VPRG_6") (pintype "bidirectional"))
    )
    (net (code "46") (name "/XERR") (class "Default")
      (node (ref "U1") (pin "23") (pinfunction "XERR_23") (pintype "bidirectional"))
      (node (ref "U2") (pin "23") (pinfunction "XERR_23") (pintype "bidirectional"))
    )
    (net (code "47") (name "/XLAT") (class "Default")
      (node (ref "SL3") (pin "4") (pinfunction "4_4") (pintype "passive"))
      (node (ref "SL5") (pin "2") (pinfunction "2_2") (pintype "passive"))
      (node (ref "U1") (pin "3") (pinfunction "XLAT_3") (pintype "bidirectional"))
      (node (ref "U2") (pin "3") (pinfunction "XLAT_3") (pintype "bidirectional"))
    )
    (net (code "48") (name "GND") (class "Default")
      (node (ref "C1") (pin "2") (pinfunction "2_2") (pintype "passive"))
      (node (ref "C2") (pin "2") (pinfunction "2_2") (pintype "passive"))
      (node (ref "IC1") (pin "GND") (pinfunction "GND_GND") (pintype "input"))
      (node (ref "R1") (pin "1") (pinfunction "1_1") (pintype "passive"))
      (node (ref "R2") (pin "1") (pinfunction "1_1") (pintype "passive"))
      (node (ref "SL6") (pin "2") (pinfunction "2_2") (pintype "passive"))
      (node (ref "U1") (pin "1") (pinfunction "GND_1") (pintype "bidirectional"))
      (node (ref "U1") (pin "29") (pinfunction "GND_29") (pintype "bidirectional"))
      (node (ref "U2") (pin "1") (pinfunction "GND_1") (pintype "bidirectional"))
      (node (ref "U2") (pin "29") (pinfunction "GND_29") (pintype "bidirectional"))
    )
    (net (code "49") (name "Net-(U1-IREF)") (class "Default")
      (node (ref "R1") (pin "2") (pinfunction "2_2") (pintype "passive"))
      (node (ref "U1") (pin "27") (pinfunction "IREF_27") (pintype "bidirectional"))
    )
    (net (code "50") (name "Net-(U2-IREF)") (class "Default")
      (node (ref "R2") (pin "2") (pinfunction "2_2") (pintype "passive"))
      (node (ref "U2") (pin "27") (pinfunction "IREF_27") (pintype "bidirectional"))
    )
    (net (code "51") (name "unconnected-(U1-OUT15-Pad22)") (class "Default")
      (node (ref "U1") (pin "22") (pinfunction "OUT15_22") (pintype "bidirectional"))
    )
    (net (code "52") (name "unconnected-(U2-OUT15-Pad22)") (class "Default")
      (node (ref "U2") (pin "22") (pinfunction "OUT15_22") (pintype "bidirectional"))
    )
  )
)
